# K0_Chrono77.net
KiCad netlist of a schematic drawn in EAGLE
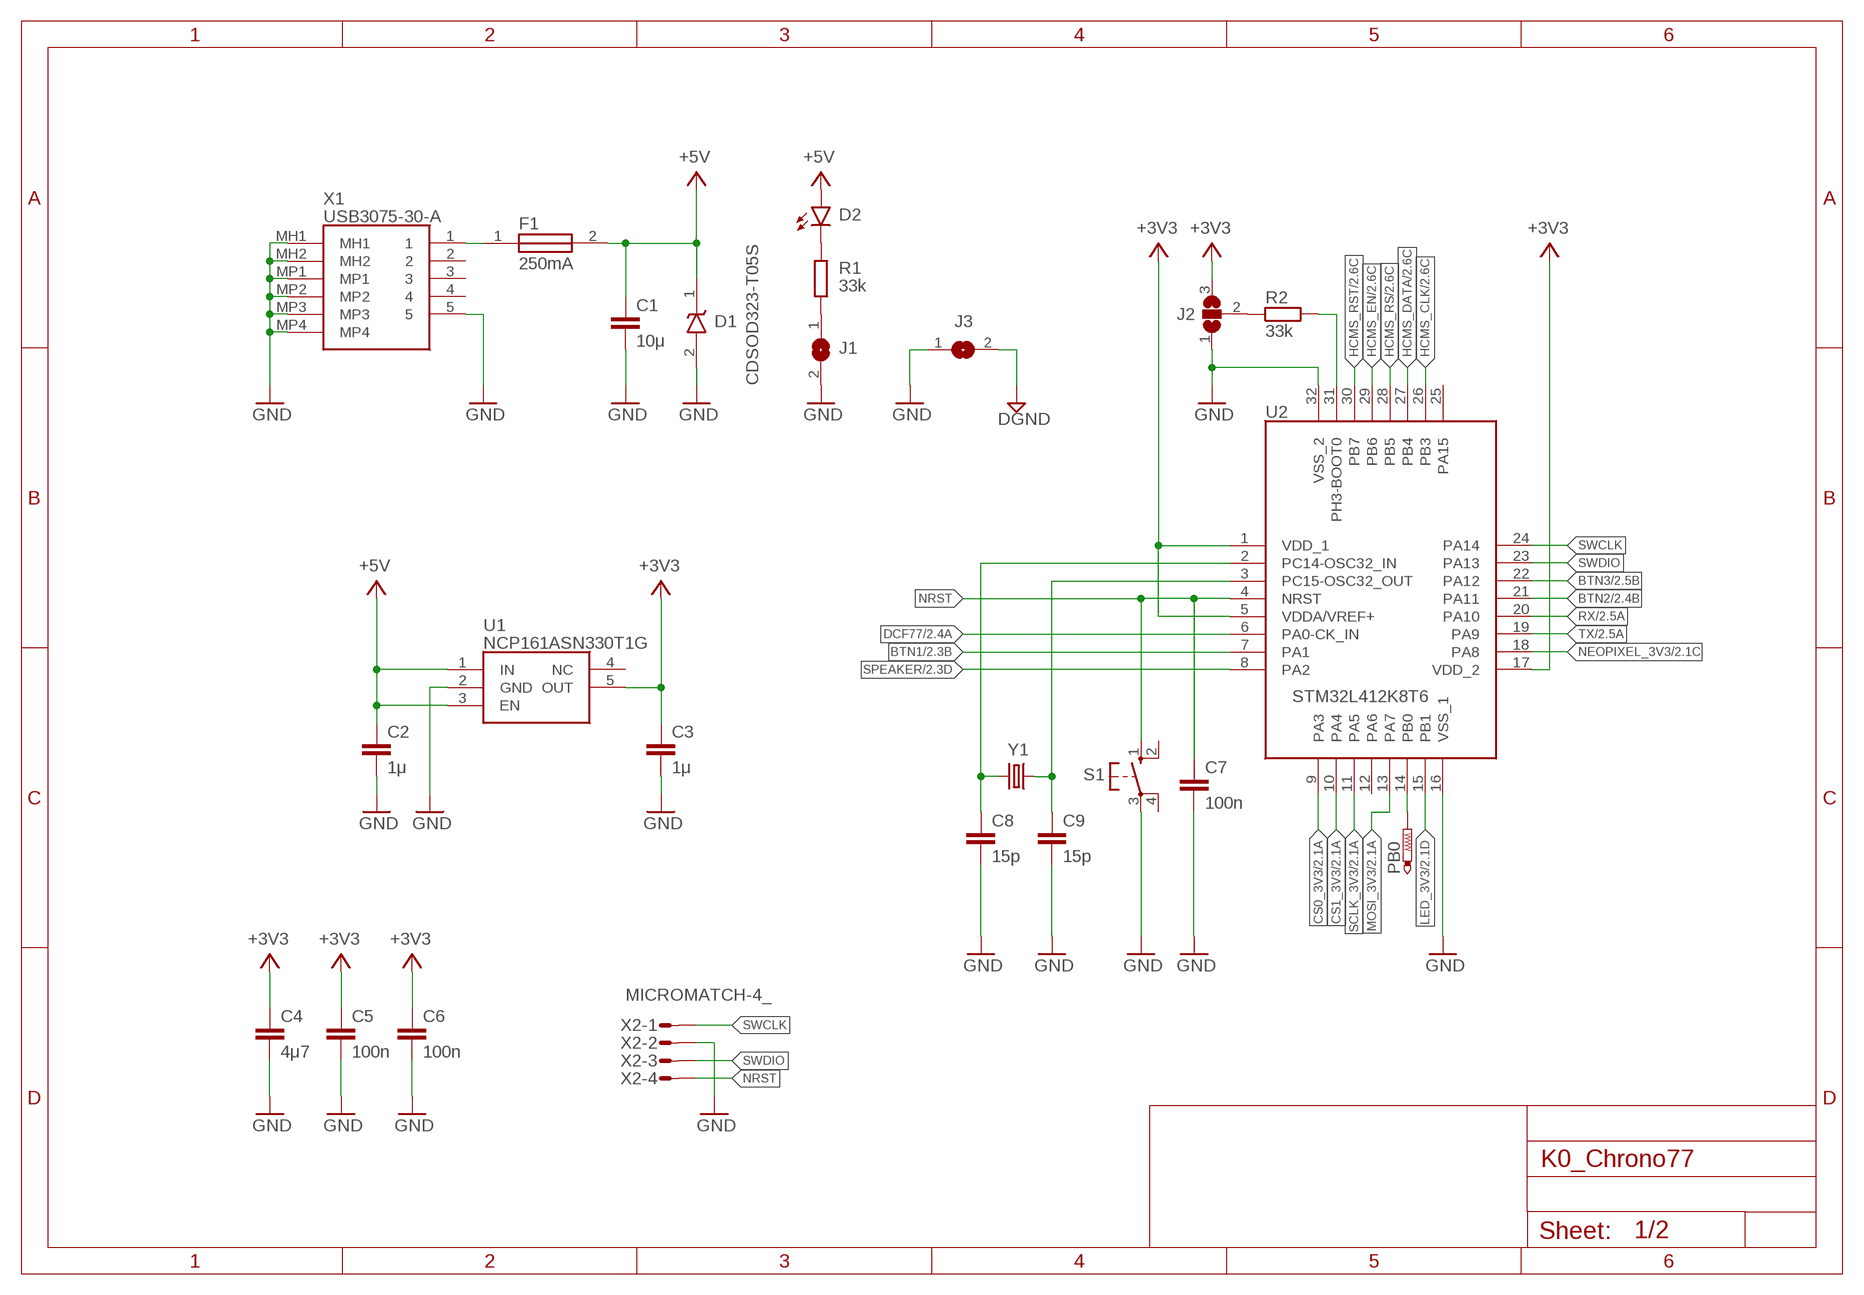
[diagram p0: schematic, sheet 1]
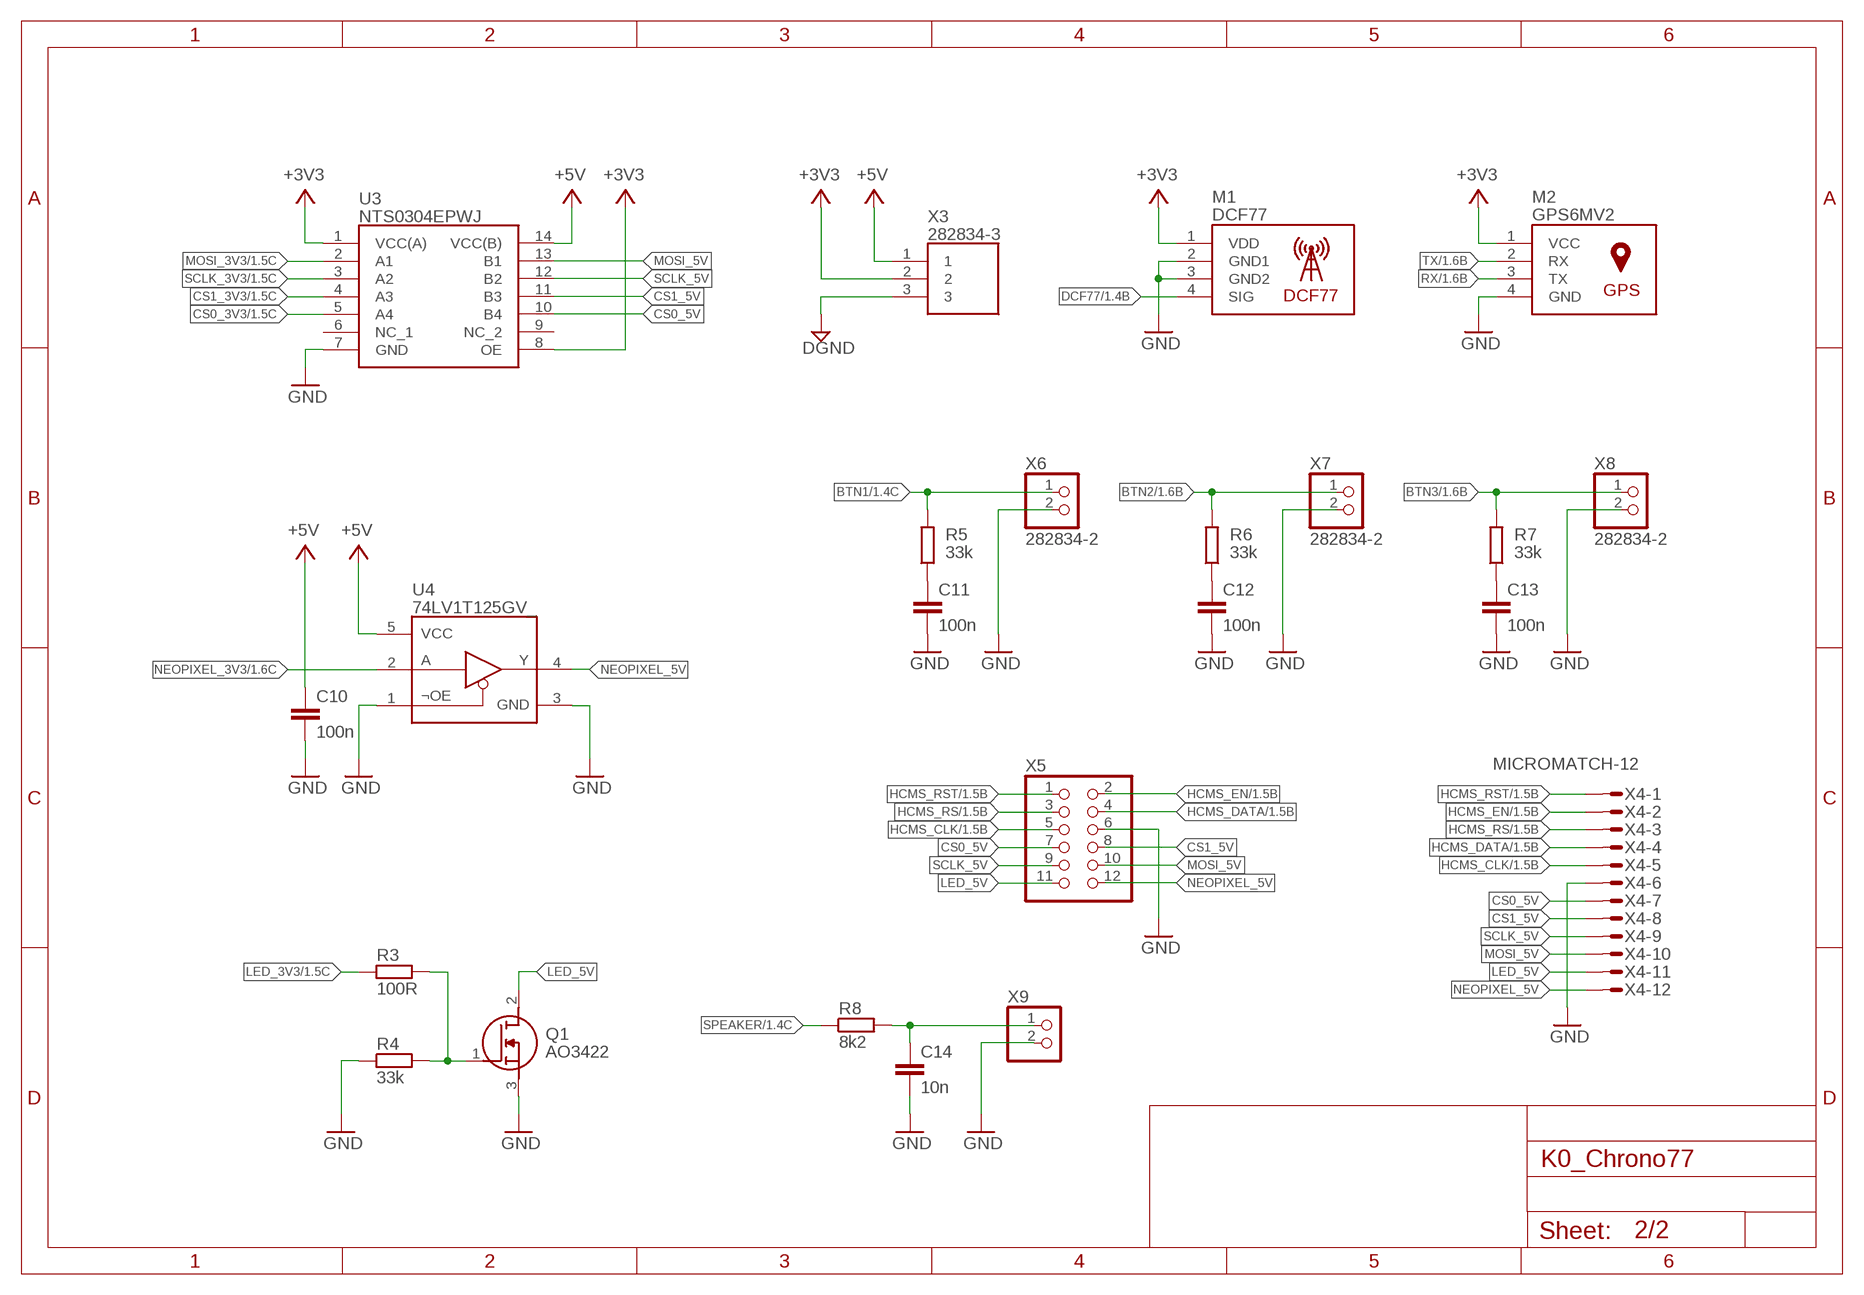
[diagram p1: schematic, sheet 2]

(export (version "E")
  (design (tool "Eeschema 10.0.6"))
  (components
    (comp (ref "C1")
      (value "10μ")
      (footprint "eagle-import:C1206")
      (libsource (lib "eagle-import") (part "C_1206C1206"))
    )
    (comp (ref "C2")
      (value "1μ")
      (footprint "eagle-import:C0805")
      (libsource (lib "eagle-import") (part "C_0805"))
    )
    (comp (ref "C3")
      (value "1μ")
      (footprint "eagle-import:C0805")
      (libsource (lib "eagle-import") (part "C_0805"))
    )
    (comp (ref "C4")
      (value "4μ7")
      (footprint "eagle-import:C0805")
      (libsource (lib "eagle-import") (part "C_0805"))
    )
    (comp (ref "C5")
      (value "100n")
      (footprint "eagle-import:C0805")
      (libsource (lib "eagle-import") (part "C_0805"))
    )
    (comp (ref "C6")
      (value "100n")
      (footprint "eagle-import:C0805")
      (libsource (lib "eagle-import") (part "C_0805"))
    )
    (comp (ref "C7")
      (value "100n")
      (footprint "eagle-import:C0805")
      (libsource (lib "eagle-import") (part "C_0805"))
    )
    (comp (ref "C8")
      (value "15p")
      (footprint "eagle-import:C0805")
      (libsource (lib "eagle-import") (part "C_0805"))
    )
    (comp (ref "C9")
      (value "15p")
      (footprint "eagle-import:C0805")
      (libsource (lib "eagle-import") (part "C_0805"))
    )
    (comp (ref "D1")
      (value "CDSOD323-T05S")
      (footprint "eagle-import:SOD2513X114N")
      (fields
        (field (name "ARROW_PART_NUMBER") "CDSOD323-T03S")
        (field (name "MOUSER_PART_NUMBER") "652-CDSOD323-T03S")
      )
      (libsource (lib "eagle-import") (part "CDSOD323-T05S"))
    )
    (comp (ref "D2")
      (value "LED_0805")
      (footprint "eagle-import:CHIP-LED0805")
      (libsource (lib "eagle-import") (part "LED_0805"))
    )
    (comp (ref "F1")
      (value "SF-2410FP150T-2")
      (footprint "eagle-import:VARC6126X270N")
      (fields (field (name "MOUSER_PART_NUMBER") "652-SF-2410FP150T-2"))
      (libsource (lib "eagle-import") (part "SF-2410FP150T-2"))
    )
    (comp (ref "J1") (value "SJ") (footprint "eagle-import:SJ") (libsource (lib "eagle-import") (part "SJ")))
    (comp (ref "J2")
      (value "SJ2W")
      (footprint "eagle-import:SJ_2")
      (libsource (lib "eagle-import") (part "SJ2W"))
    )
    (comp (ref "J3") (value "SJ") (footprint "eagle-import:SJ") (libsource (lib "eagle-import") (part "SJ")))
    (comp (ref "PB0")
      (value "PTR1TP14R")
      (footprint "eagle-import:TP14R")
      (libsource (lib "eagle-import") (part "PTR1TP14R"))
    )
    (comp (ref "R1")
      (value "33k")
      (footprint "eagle-import:R0805")
      (libsource (lib "eagle-import") (part "R_0805"))
    )
    (comp (ref "R2")
      (value "33k")
      (footprint "eagle-import:R0805")
      (libsource (lib "eagle-import") (part "R_0805"))
    )
    (comp (ref "S1")
      (value "10-XX")
      (footprint "eagle-import:B3F-10XX")
      (fields (field (name "MPN") "B3F-1000"))
      (libsource (lib "eagle-import") (part "10-XX"))
    )
    (comp (ref "U1")
      (value "NCP161ASN330T1G")
      (footprint "eagle-import:SOT95P280X145-5N")
      (fields (field (name "MOUSER_PART_NUMBER") "863-NCP161ASN330T1G"))
      (libsource (lib "eagle-import") (part "NCP161ASN330T1G"))
    )
    (comp (ref "U2")
      (value "STM32L412K8T6")
      (footprint "eagle-import:QFP80P900X900X160-32N")
      (fields (field (name "MOUSER_PART_NUMBER") "511-STM32L412K8T6"))
      (libsource (lib "eagle-import") (part "STM32L412K8T6"))
    )
    (comp (ref "X1")
      (value "USB3075-30-A")
      (footprint "eagle-import:USB307530A")
      (fields (field (name "MOUSER_PART_NUMBER") "640-USB3075-30-A"))
      (libsource (lib "eagle-import") (part "USB3075-30-A"))
    )
    (comp (ref "X2")
      (value "MICROMATCH-4_")
      (footprint "eagle-import:MICROMATCH-4")
      (libsource (lib "eagle-import") (part "MICROMATCH-4_"))
    )
    (comp (ref "Y1")
      (value "CRYSTALTC26H")
      (footprint "eagle-import:TC26H")
      (libsource (lib "eagle-import") (part "CRYSTALTC26H"))
    )
    (comp (ref "C10")
      (value "100n")
      (footprint "eagle-import:C0805")
      (libsource (lib "eagle-import") (part "C_0805"))
    )
    (comp (ref "C11")
      (value "100n")
      (footprint "eagle-import:C0805")
      (libsource (lib "eagle-import") (part "C_0805"))
    )
    (comp (ref "C12")
      (value "100n")
      (footprint "eagle-import:C0805")
      (libsource (lib "eagle-import") (part "C_0805"))
    )
    (comp (ref "C13")
      (value "100n")
      (footprint "eagle-import:C0805")
      (libsource (lib "eagle-import") (part "C_0805"))
    )
    (comp (ref "C14")
      (value "10n")
      (footprint "eagle-import:C0805")
      (libsource (lib "eagle-import") (part "C_0805"))
    )
    (comp (ref "M1")
      (value "DCF77")
      (footprint "eagle-import:DCF77")
      (libsource (lib "eagle-import") (part "DCF77"))
    )
    (comp (ref "M2")
      (value "GPS6MV2")
      (footprint "eagle-import:GPS6MV2")
      (libsource (lib "eagle-import") (part "GPS6MV2"))
    )
    (comp (ref "Q1")
      (value "AO3422")
      (footprint "eagle-import:SOT95P237X112-3N")
      (libsource (lib "eagle-import") (part "AO3422"))
    )
    (comp (ref "R3")
      (value "100R")
      (footprint "eagle-import:R0805")
      (libsource (lib "eagle-import") (part "R_0805"))
    )
    (comp (ref "R4")
      (value "33k")
      (footprint "eagle-import:R0805")
      (libsource (lib "eagle-import") (part "R_0805"))
    )
    (comp (ref "R5")
      (value "33k")
      (footprint "eagle-import:R0805")
      (libsource (lib "eagle-import") (part "R_0805"))
    )
    (comp (ref "R6")
      (value "33k")
      (footprint "eagle-import:R0805")
      (libsource (lib "eagle-import") (part "R_0805"))
    )
    (comp (ref "R7")
      (value "33k")
      (footprint "eagle-import:R0805")
      (libsource (lib "eagle-import") (part "R_0805"))
    )
    (comp (ref "R8")
      (value "8k2")
      (footprint "eagle-import:R0805")
      (libsource (lib "eagle-import") (part "R_0805"))
    )
    (comp (ref "U3")
      (value "NTS0304EPWJ")
      (footprint "eagle-import:SOP65P640X110-14N")
      (fields (field (name "MOUSER_PART_NUMBER") "771-NTS0304EPWJ"))
      (libsource (lib "eagle-import") (part "NTS0304EPWJ"))
    )
    (comp (ref "U4")
      (value "74LV1T125GV_")
      (footprint "eagle-import:SOT753")
      (libsource (lib "eagle-import") (part "74LV1T125GV_"))
    )
    (comp (ref "X3")
      (value "282834-3")
      (footprint "eagle-import:SHDR3W100P0X254_1X3_808X650X10")
      (fields (field (name "MOUSER_PART_NUMBER") "571-2828343") (field (name "RS_PART_NUMBER") "1640792"))
      (libsource (lib "eagle-import") (part "282834-3"))
    )
    (comp (ref "X4")
      (value "MICROMATCH-12")
      (footprint "eagle-import:MICROMATCH-12")
      (fields (field (name "MF") "FARNELL") (field (name "MPN") "8-215464-2"))
      (libsource (lib "eagle-import") (part "MICROMATCH-12"))
    )
    (comp (ref "X5")
      (value "PINHD-2X6")
      (footprint "eagle-import:2X06")
      (libsource (lib "eagle-import") (part "PINHD-2X6"))
    )
    (comp (ref "X6")
      (value "282834-2")
      (footprint "eagle-import:SHDR2W85P0X254_1X2_554X650X103")
      (libsource (lib "eagle-import") (part "282834-2"))
    )
    (comp (ref "X7")
      (value "282834-2")
      (footprint "eagle-import:SHDR2W85P0X254_1X2_554X650X103")
      (libsource (lib "eagle-import") (part "282834-2"))
    )
    (comp (ref "X8")
      (value "282834-2")
      (footprint "eagle-import:SHDR2W85P0X254_1X2_554X650X103")
      (libsource (lib "eagle-import") (part "282834-2"))
    )
    (comp (ref "X9")
      (value "PINHD-1X2/90")
      (footprint "eagle-import:1X02_90")
      (libsource (lib "eagle-import") (part "PINHD-1X2/90"))
    )
  )
  (nets
    (net (code "1") (name "+3V3") (class "Default")
      (node (ref "C3") (pin "1") (pinfunction "1_1") (pintype "passive"))
      (node (ref "C4") (pin "1") (pinfunction "1_1") (pintype "passive"))
      (node (ref "C5") (pin "1") (pinfunction "1_1") (pintype "passive"))
      (node (ref "C6") (pin "1") (pinfunction "1_1") (pintype "passive"))
      (node (ref "J2") (pin "3") (pinfunction "3_3") (pintype "passive"))
      (node (ref "M1") (pin "1") (pinfunction "VDD_1") (pintype "bidirectional"))
      (node (ref "M2") (pin "1") (pinfunction "VCC_1") (pintype "bidirectional"))
      (node (ref "U1") (pin "5") (pinfunction "OUT_5") (pintype "bidirectional"))
      (node (ref "U2") (pin "1") (pinfunction "VDD_1_1") (pintype "bidirectional"))
      (node (ref "U2") (pin "17") (pinfunction "VDD_2_17") (pintype "bidirectional"))
      (node (ref "U2") (pin "5") (pinfunction "VDDA/VREF+_5") (pintype "bidirectional"))
      (node (ref "U3") (pin "1") (pinfunction "VCC(A)_1") (pintype "power_in"))
      (node (ref "U3") (pin "8") (pinfunction "OE_8") (pintype "input"))
      (node (ref "X3") (pin "2") (pinfunction "2_2") (pintype "bidirectional"))
    )
    (net (code "2") (name "+5V") (class "Default")
      (node (ref "C1") (pin "1") (pinfunction "1_1") (pintype "passive"))
      (node (ref "C10") (pin "1") (pinfunction "1_1") (pintype "passive"))
      (node (ref "C2") (pin "1") (pinfunction "1_1") (pintype "passive"))
      (node (ref "D1") (pin "1") (pinfunction "K_1") (pintype "bidirectional"))
      (node (ref "D2") (pin "A") (pinfunction "A_A") (pintype "passive"))
      (node (ref "F1") (pin "2") (pinfunction "2_2") (pintype "bidirectional"))
      (node (ref "U1") (pin "1") (pinfunction "IN_1") (pintype "bidirectional"))
      (node (ref "U1") (pin "3") (pinfunction "EN_3") (pintype "bidirectional"))
      (node (ref "U3") (pin "14") (pinfunction "VCC(B)_14") (pintype "power_in"))
      (node (ref "U4") (pin "5") (pinfunction "VCC_5") (pintype "bidirectional"))
      (node (ref "X3") (pin "1") (pinfunction "1_1") (pintype "bidirectional"))
    )
    (net (code "3") (name "BTN1") (class "Default")
      (node (ref "R5") (pin "2") (pinfunction "2_2") (pintype "passive"))
      (node (ref "U2") (pin "7") (pinfunction "PA1_7") (pintype "bidirectional"))
      (node (ref "X6") (pin "1") (pinfunction "1_1") (pintype "passive"))
    )
    (net (code "4") (name "BTN2") (class "Default")
      (node (ref "R6") (pin "2") (pinfunction "2_2") (pintype "passive"))
      (node (ref "U2") (pin "21") (pinfunction "PA11_21") (pintype "bidirectional"))
      (node (ref "X7") (pin "1") (pinfunction "1_1") (pintype "passive"))
    )
    (net (code "5") (name "BTN3") (class "Default")
      (node (ref "R7") (pin "2") (pinfunction "2_2") (pintype "passive"))
      (node (ref "U2") (pin "22") (pinfunction "PA12_22") (pintype "bidirectional"))
      (node (ref "X8") (pin "1") (pinfunction "1_1") (pintype "passive"))
    )
    (net (code "6") (name "CS0_3V3") (class "Default")
      (node (ref "U2") (pin "9") (pinfunction "PA3_9") (pintype "bidirectional"))
      (node (ref "U3") (pin "5") (pinfunction "A4_5") (pintype "bidirectional"))
    )
    (net (code "7") (name "CS0_5V") (class "Default")
      (node (ref "U3") (pin "10") (pinfunction "B4_10") (pintype "bidirectional"))
      (node (ref "X4") (pin "7") (pinfunction "S_7") (pintype "passive"))
      (node (ref "X5") (pin "7") (pinfunction "7_7") (pintype "passive"))
    )
    (net (code "8") (name "CS1_3V3") (class "Default")
      (node (ref "U2") (pin "10") (pinfunction "PA4_10") (pintype "bidirectional"))
      (node (ref "U3") (pin "4") (pinfunction "A3_4") (pintype "bidirectional"))
    )
    (net (code "9") (name "CS1_5V") (class "Default")
      (node (ref "U3") (pin "11") (pinfunction "B3_11") (pintype "bidirectional"))
      (node (ref "X4") (pin "8") (pinfunction "S_8") (pintype "passive"))
      (node (ref "X5") (pin "8") (pinfunction "8_8") (pintype "passive"))
    )
    (net (code "10") (name "DCF77") (class "Default")
      (node (ref "M1") (pin "4") (pinfunction "SIG_4") (pintype "bidirectional"))
      (node (ref "U2") (pin "6") (pinfunction "PA0-CK_IN_6") (pintype "bidirectional"))
    )
    (net (code "11") (name "DGND") (class "Default")
      (node (ref "J3") (pin "2") (pinfunction "2_2") (pintype "passive"))
      (node (ref "X3") (pin "3") (pinfunction "3_3") (pintype "bidirectional"))
    )
    (net (code "12") (name "GND") (class "Default")
      (node (ref "C1") (pin "2") (pinfunction "2_2") (pintype "passive"))
      (node (ref "C10") (pin "2") (pinfunction "2_2") (pintype "passive"))
      (node (ref "C11") (pin "2") (pinfunction "2_2") (pintype "passive"))
      (node (ref "C12") (pin "2") (pinfunction "2_2") (pintype "passive"))
      (node (ref "C13") (pin "2") (pinfunction "2_2") (pintype "passive"))
      (node (ref "C14") (pin "2") (pinfunction "2_2") (pintype "passive"))
      (node (ref "C2") (pin "2") (pinfunction "2_2") (pintype "passive"))
      (node (ref "C3") (pin "2") (pinfunction "2_2") (pintype "passive"))
      (node (ref "C4") (pin "2") (pinfunction "2_2") (pintype "passive"))
      (node (ref "C5") (pin "2") (pinfunction "2_2") (pintype "passive"))
      (node (ref "C6") (pin "2") (pinfunction "2_2") (pintype "passive"))
      (node (ref "C7") (pin "2") (pinfunction "2_2") (pintype "passive"))
      (node (ref "C8") (pin "2") (pinfunction "2_2") (pintype "passive"))
      (node (ref "C9") (pin "2") (pinfunction "2_2") (pintype "passive"))
      (node (ref "D1") (pin "2") (pinfunction "A_2") (pintype "bidirectional"))
      (node (ref "J1") (pin "2") (pinfunction "2_2") (pintype "passive"))
      (node (ref "J2") (pin "1") (pinfunction "1_1") (pintype "passive"))
      (node (ref "J3") (pin "1") (pinfunction "1_1") (pintype "passive"))
      (node (ref "M1") (pin "2") (pinfunction "GND1_2") (pintype "bidirectional"))
      (node (ref "M1") (pin "3") (pinfunction "GND2_3") (pintype "bidirectional"))
      (node (ref "M2") (pin "4") (pinfunction "GND_4") (pintype "bidirectional"))
      (node (ref "Q1") (pin "3") (pinfunction "S_3") (pintype "bidirectional"))
      (node (ref "R4") (pin "1") (pinfunction "1_1") (pintype "passive"))
      (node (ref "S1") (pin "3") (pinfunction "P_3") (pintype "passive"))
      (node (ref "U1") (pin "2") (pinfunction "GND_2") (pintype "power_in"))
      (node (ref "U2") (pin "16") (pinfunction "VSS_1_16") (pintype "bidirectional"))
      (node (ref "U2") (pin "32") (pinfunction "VSS_2_32") (pintype "bidirectional"))
      (node (ref "U3") (pin "7") (pinfunction "GND_7") (pintype "power_in"))
      (node (ref "U4") (pin "1") (pinfunction "¬OE_1") (pintype "bidirectional"))
      (node (ref "U4") (pin "3") (pinfunction "GND_3") (pintype "bidirectional"))
      (node (ref "X1") (pin "5") (pinfunction "5_5") (pintype "bidirectional"))
      (node (ref "X1") (pin "MH1") (pinfunction "MH1_MH1") (pintype "bidirectional"))
      (node (ref "X1") (pin "MH2") (pinfunction "MH2_MH2") (pintype "bidirectional"))
      (node (ref "X1") (pin "MP1") (pinfunction "MP1_MP1") (pintype "bidirectional"))
      (node (ref "X1") (pin "MP2") (pinfunction "MP2_MP2") (pintype "bidirectional"))
      (node (ref "X1") (pin "MP3") (pinfunction "MP3_MP3") (pintype "bidirectional"))
      (node (ref "X1") (pin "MP4") (pinfunction "MP4_MP4") (pintype "bidirectional"))
      (node (ref "X2") (pin "2") (pinfunction "S_2") (pintype "passive"))
      (node (ref "X4") (pin "6") (pinfunction "S_6") (pintype "passive"))
      (node (ref "X5") (pin "6") (pinfunction "6_6") (pintype "passive"))
      (node (ref "X6") (pin "2") (pinfunction "2_2") (pintype "passive"))
      (node (ref "X7") (pin "2") (pinfunction "2_2") (pintype "passive"))
      (node (ref "X8") (pin "2") (pinfunction "2_2") (pintype "passive"))
      (node (ref "X9") (pin "2") (pinfunction "2_2") (pintype "passive"))
    )
    (net (code "13") (name "HCMS_CLK") (class "Default")
      (node (ref "U2") (pin "26") (pinfunction "PB3_26") (pintype "bidirectional"))
      (node (ref "X4") (pin "5") (pinfunction "S_5") (pintype "passive"))
      (node (ref "X5") (pin "5") (pinfunction "5_5") (pintype "passive"))
    )
    (net (code "14") (name "HCMS_DATA") (class "Default")
      (node (ref "U2") (pin "27") (pinfunction "PB4_27") (pintype "bidirectional"))
      (node (ref "X4") (pin "4") (pinfunction "S_4") (pintype "passive"))
      (node (ref "X5") (pin "4") (pinfunction "4_4") (pintype "passive"))
    )
    (net (code "15") (name "HCMS_EN") (class "Default")
      (node (ref "U2") (pin "29") (pinfunction "PB6_29") (pintype "bidirectional"))
      (node (ref "X4") (pin "2") (pinfunction "S_2") (pintype "passive"))
      (node (ref "X5") (pin "2") (pinfunction "2_2") (pintype "passive"))
    )
    (net (code "16") (name "HCMS_RS") (class "Default")
      (node (ref "U2") (pin "28") (pinfunction "PB5_28") (pintype "bidirectional"))
      (node (ref "X4") (pin "3") (pinfunction "S_3") (pintype "passive"))
      (node (ref "X5") (pin "3") (pinfunction "3_3") (pintype "passive"))
    )
    (net (code "17") (name "HCMS_RST") (class "Default")
      (node (ref "U2") (pin "30") (pinfunction "PB7_30") (pintype "bidirectional"))
      (node (ref "X4") (pin "1") (pinfunction "S_1") (pintype "passive"))
      (node (ref "X5") (pin "1") (pinfunction "1_1") (pintype "passive"))
    )
    (net (code "18") (name "LED_3V3") (class "Default")
      (node (ref "R3") (pin "1") (pinfunction "1_1") (pintype "passive"))
      (node (ref "U2") (pin "15") (pinfunction "PB1_15") (pintype "bidirectional"))
    )
    (net (code "19") (name "LED_5V") (class "Default")
      (node (ref "Q1") (pin "2") (pinfunction "D_2") (pintype "bidirectional"))
      (node (ref "X4") (pin "11") (pinfunction "S_11") (pintype "passive"))
      (node (ref "X5") (pin "11") (pinfunction "11_11") (pintype "passive"))
    )
    (net (code "20") (name "MOSI_3V3") (class "Default")
      (node (ref "U2") (pin "13") (pinfunction "PA7_13") (pintype "bidirectional"))
      (node (ref "U3") (pin "2") (pinfunction "A1_2") (pintype "bidirectional"))
    )
    (net (code "21") (name "MOSI_5V") (class "Default")
      (node (ref "U3") (pin "13") (pinfunction "B1_13") (pintype "bidirectional"))
      (node (ref "X4") (pin "10") (pinfunction "S_10") (pintype "passive"))
      (node (ref "X5") (pin "10") (pinfunction "10_10") (pintype "passive"))
    )
    (net (code "22") (name "NEOPIXEL_3V3") (class "Default")
      (node (ref "U2") (pin "18") (pinfunction "PA8_18") (pintype "bidirectional"))
      (node (ref "U4") (pin "2") (pinfunction "A_2") (pintype "bidirectional"))
    )
    (net (code "23") (name "NEOPIXEL_5V") (class "Default")
      (node (ref "U4") (pin "4") (pinfunction "Y_4") (pintype "bidirectional"))
      (node (ref "X4") (pin "12") (pinfunction "S_12") (pintype "passive"))
      (node (ref "X5") (pin "12") (pinfunction "12_12") (pintype "passive"))
    )
    (net (code "24") (name "NRST") (class "Default")
      (node (ref "C7") (pin "1") (pinfunction "1_1") (pintype "passive"))
      (node (ref "S1") (pin "1") (pinfunction "S_1") (pintype "passive"))
      (node (ref "U2") (pin "4") (pinfunction "NRST_4") (pintype "bidirectional"))
      (node (ref "X2") (pin "4") (pinfunction "S_4") (pintype "passive"))
    )
    (net (code "25") (name "Net-(C11-Pad1)") (class "Default")
      (node (ref "C11") (pin "1") (pinfunction "1_1") (pintype "passive"))
      (node (ref "R5") (pin "1") (pinfunction "1_1") (pintype "passive"))
    )
    (net (code "26") (name "Net-(C12-Pad1)") (class "Default")
      (node (ref "C12") (pin "1") (pinfunction "1_1") (pintype "passive"))
      (node (ref "R6") (pin "1") (pinfunction "1_1") (pintype "passive"))
    )
    (net (code "27") (name "Net-(C13-Pad1)") (class "Default")
      (node (ref "C13") (pin "1") (pinfunction "1_1") (pintype "passive"))
      (node (ref "R7") (pin "1") (pinfunction "1_1") (pintype "passive"))
    )
    (net (code "28") (name "Net-(C14-Pad1)") (class "Default")
      (node (ref "C14") (pin "1") (pinfunction "1_1") (pintype "passive"))
      (node (ref "R8") (pin "2") (pinfunction "2_2") (pintype "passive"))
      (node (ref "X9") (pin "1") (pinfunction "1_1") (pintype "passive"))
    )
    (net (code "29") (name "Net-(D2-PadC)") (class "Default")
      (node (ref "D2") (pin "C") (pinfunction "C_C") (pintype "passive"))
      (node (ref "R1") (pin "2") (pinfunction "2_2") (pintype "passive"))
    )
    (net (code "30") (name "Net-(F1-Pad1)") (class "Default")
      (node (ref "F1") (pin "1") (pinfunction "1_1") (pintype "bidirectional"))
      (node (ref "X1") (pin "1") (pinfunction "1_1") (pintype "bidirectional"))
    )
    (net (code "31") (name "Net-(J1-Pad1)") (class "Default")
      (node (ref "J1") (pin "1") (pinfunction "1_1") (pintype "passive"))
      (node (ref "R1") (pin "1") (pinfunction "1_1") (pintype "passive"))
    )
    (net (code "32") (name "Net-(J2-Pad2)") (class "Default")
      (node (ref "J2") (pin "2") (pinfunction "2_2") (pintype "passive"))
      (node (ref "R2") (pin "1") (pinfunction "1_1") (pintype "passive"))
    )
    (net (code "33") (name "Net-(Q1-G)") (class "Default")
      (node (ref "Q1") (pin "1") (pinfunction "G_1") (pintype "bidirectional"))
      (node (ref "R3") (pin "2") (pinfunction "2_2") (pintype "passive"))
      (node (ref "R4") (pin "2") (pinfunction "2_2") (pintype "passive"))
    )
    (net (code "34") (name "Net-(U2-PB0)") (class "Default")
      (node (ref "PB0") (pin "TP") (pinfunction "TP_TP") (pintype "input"))
      (node (ref "U2") (pin "14") (pinfunction "PB0_14") (pintype "bidirectional"))
    )
    (net (code "35") (name "Net-(U2-PC14-OSC32_IN)") (class "Default")
      (node (ref "C8") (pin "1") (pinfunction "1_1") (pintype "passive"))
      (node (ref "U2") (pin "2") (pinfunction "PC14-OSC32_IN_2") (pintype "bidirectional"))
      (node (ref "Y1") (pin "2") (pinfunction "2_2") (pintype "passive"))
    )
    (net (code "36") (name "Net-(U2-PC15-OSC32_OUT)") (class "Default")
      (node (ref "C9") (pin "1") (pinfunction "1_1") (pintype "passive"))
      (node (ref "U2") (pin "3") (pinfunction "PC15-OSC32_OUT_3") (pintype "bidirectional"))
      (node (ref "Y1") (pin "1") (pinfunction "1_1") (pintype "passive"))
    )
    (net (code "37") (name "Net-(U2-PH3-BOOT0)") (class "Default")
      (node (ref "R2") (pin "2") (pinfunction "2_2") (pintype "passive"))
      (node (ref "U2") (pin "31") (pinfunction "PH3-BOOT0_31") (pintype "bidirectional"))
    )
    (net (code "38") (name "RX") (class "Default")
      (node (ref "M2") (pin "3") (pinfunction "TX_3") (pintype "bidirectional"))
      (node (ref "U2") (pin "20") (pinfunction "PA10_20") (pintype "bidirectional"))
    )
    (net (code "39") (name "SCLK_3V3") (class "Default")
      (node (ref "U2") (pin "11") (pinfunction "PA5_11") (pintype "bidirectional"))
      (node (ref "U3") (pin "3") (pinfunction "A2_3") (pintype "bidirectional"))
    )
    (net (code "40") (name "SCLK_5V") (class "Default")
      (node (ref "U3") (pin "12") (pinfunction "B2_12") (pintype "bidirectional"))
      (node (ref "X4") (pin "9") (pinfunction "S_9") (pintype "passive"))
      (node (ref "X5") (pin "9") (pinfunction "9_9") (pintype "passive"))
    )
    (net (code "41") (name "SPEAKER") (class "Default")
      (node (ref "R8") (pin "1") (pinfunction "1_1") (pintype "passive"))
      (node (ref "U2") (pin "8") (pinfunction "PA2_8") (pintype "bidirectional"))
    )
    (net (code "42") (name "SWCLK") (class "Default")
      (node (ref "U2") (pin "24") (pinfunction "PA14_24") (pintype "bidirectional"))
      (node (ref "X2") (pin "1") (pinfunction "S_1") (pintype "passive"))
    )
    (net (code "43") (name "SWDIO") (class "Default")
      (node (ref "U2") (pin "23") (pinfunction "PA13_23") (pintype "bidirectional"))
      (node (ref "X2") (pin "3") (pinfunction "S_3") (pintype "passive"))
    )
    (net (code "44") (name "TX") (class "Default")
      (node (ref "M2") (pin "2") (pinfunction "RX_2") (pintype "bidirectional"))
      (node (ref "U2") (pin "19") (pinfunction "PA9_19") (pintype "bidirectional"))
    )
    (net (code "45") (name "unconnected-(S1-P1-Pad4)") (class "Default")
      (node (ref "S1") (pin "4") (pinfunction "P1_4") (pintype "passive"))
    )
    (net (code "46") (name "unconnected-(S1-S1-Pad2)") (class "Default")
      (node (ref "S1") (pin "2") (pinfunction "S1_2") (pintype "passive"))
    )
    (net (code "47") (name "unconnected-(U1-NC-Pad4)") (class "Default")
      (node (ref "U1") (pin "4") (pinfunction "NC_4") (pintype "no_connect"))
    )
    (net (code "48") (name "unconnected-(U2-PA6-Pad12)") (class "Default")
      (node (ref "U2") (pin "12") (pinfunction "PA6_12") (pintype "bidirectional"))
    )
    (net (code "49") (name "unconnected-(U2-PA15-Pad25)") (class "Default")
      (node (ref "U2") (pin "25") (pinfunction "PA15_25") (pintype "bidirectional"))
    )
    (net (code "50") (name "unconnected-(U3-NC_1-Pad6)") (class "Default")
      (node (ref "U3") (pin "6") (pinfunction "NC_1_6") (pintype "bidirectional"))
    )
    (net (code "51") (name "unconnected-(U3-NC_2-Pad9)") (class "Default")
      (node (ref "U3") (pin "9") (pinfunction "NC_2_9") (pintype "bidirectional"))
    )
    (net (code "52") (name "unconnected-(X1-Pad2)") (class "Default")
      (node (ref "X1") (pin "2") (pinfunction "2_2") (pintype "bidirectional"))
    )
    (net (code "53") (name "unconnected-(X1-Pad3)") (class "Default")
      (node (ref "X1") (pin "3") (pinfunction "3_3") (pintype "bidirectional"))
    )
    (net (code "54") (name "unconnected-(X1-Pad4)") (class "Default")
      (node (ref "X1") (pin "4") (pinfunction "4_4") (pintype "bidirectional"))
    )
  )
)
